# dcmotorR.net
KiCad netlist of a schematic drawn in EAGLE
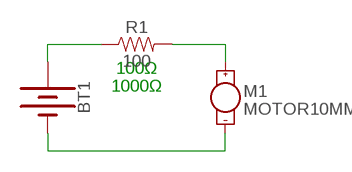
[diagram p0: schematic, sheet 1]

(export (version "E")
  (design (tool "Eeschema 10.0.6"))
  (components
    (comp (ref "BT1")
      (value "BATTERY-9V")
      (footprint "eagle-import:BATTCON_9V")
      (libsource (lib "eagle-import") (part "BATTERY-9V"))
    )
    (comp (ref "M1")
      (value "MOTOR10MM")
      (footprint "eagle-import:VIBE-MOTOR-10MM")
      (libsource (lib "eagle-import") (part "MOTOR10MM"))
    )
    (comp (ref "R1")
      (value "100")
      (footprint "eagle-import:AXIAL-0.3")
      (libsource (lib "eagle-import") (part "100OHM-HORIZ-1/4W-1%"))
    )
  )
  (nets
    (net (code "1") (name "Net-(BT1-Pad-)") (class "Default")
      (node (ref "BT1") (pin "-") (pinfunction "-_-") (pintype "power_in"))
      (node (ref "M1") (pin "-") (pinfunction "-_-") (pintype "bidirectional"))
    )
    (net (code "2") (name "Net-(R1-1)") (class "Default")
      (node (ref "BT1") (pin "+") (pinfunction "+_+") (pintype "power_in"))
      (node (ref "R1") (pin "P$1") (pinfunction "1_P$1") (pintype "passive"))
    )
    (net (code "3") (name "Net-(R1-2)") (class "Default")
      (node (ref "M1") (pin "+") (pinfunction "+_+") (pintype "bidirectional"))
      (node (ref "R1") (pin "P$2") (pinfunction "2_P$2") (pintype "passive"))
    )
  )
)
